# 9V_Power_Supply.net
KiCad netlist of a schematic drawn in EAGLE
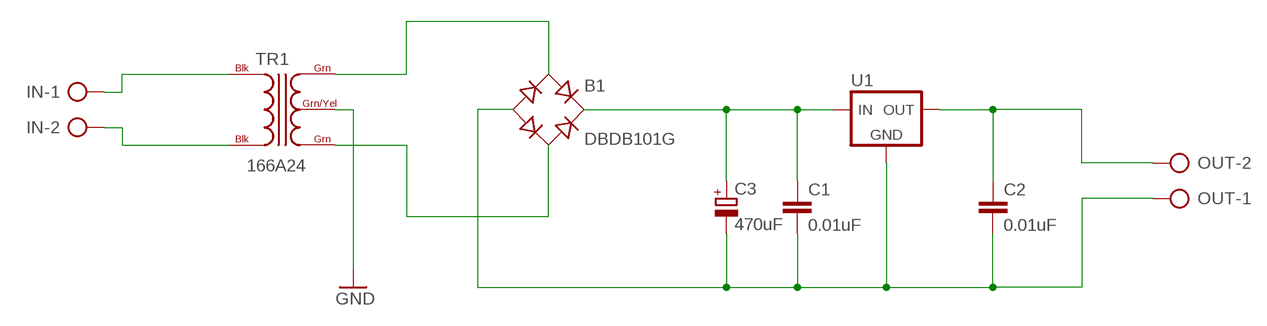
[diagram p0: schematic, sheet 1]

(export (version "E")
  (design (tool "Eeschema 10.0.6"))
  (components
    (comp (ref "B1")
      (value "DBDB101G")
      (footprint "eagle-import:DB")
      (libsource (lib "eagle-import") (part "DB?GDB101"))
    )
    (comp (ref "C1")
      (value "0.01uF")
      (footprint "eagle-import:C025-030X050")
      (libsource (lib "eagle-import") (part "C-EU025-030X050"))
    )
    (comp (ref "C2")
      (value "0.01uF")
      (footprint "eagle-import:C025-030X050")
      (libsource (lib "eagle-import") (part "C-EU025-030X050"))
    )
    (comp (ref "C3")
      (value "470uF")
      (footprint "eagle-import:E2,5-7")
      (libsource (lib "eagle-import") (part "CPOL-EUE2.5-7"))
    )
    (comp (ref "IN")
      (value "AK300/2")
      (footprint "eagle-import:AK300_2")
      (libsource (lib "eagle-import") (part "AK300/2"))
    )
    (comp (ref "OUT")
      (value "AK300/2")
      (footprint "eagle-import:AK300_2")
      (libsource (lib "eagle-import") (part "AK300/2"))
    )
    (comp (ref "TR1")
      (value "166A24")
      (footprint "eagle-import:C2H")
      (libsource (lib "eagle-import") (part "166A24"))
    )
    (comp (ref "U1")
      (value "78XX-TO220H-NH")
      (footprint "eagle-import:TO220BH-NH")
      (libsource (lib "eagle-import") (part "78XX-TO220H-NH"))
    )
  )
  (nets
    (net (code "1") (name "GND") (class "Default")
      (node (ref "B1") (pin "-") (pinfunction "-_-") (pintype "passive"))
      (node (ref "C1") (pin "2") (pinfunction "2_2") (pintype "passive"))
      (node (ref "C2") (pin "2") (pinfunction "2_2") (pintype "passive"))
      (node (ref "C3") (pin "-") (pinfunction "-_-") (pintype "passive"))
      (node (ref "OUT") (pin "1") (pinfunction "KL_1") (pintype "passive"))
      (node (ref "TR1") (pin "GRN/YEL") (pinfunction "GRN/YEL_GRN/YEL") (pintype "passive"))
      (node (ref "U1") (pin "2") (pinfunction "GND_2") (pintype "power_in"))
    )
    (net (code "2") (name "Net-(B1-PadAC1)") (class "Default")
      (node (ref "B1") (pin "AC1") (pinfunction "AC1_AC1") (pintype "passive"))
      (node (ref "TR1") (pin "GRN@1") (pinfunction "GRN_GRN@1") (pintype "passive"))
    )
    (net (code "3") (name "Net-(B1-PadAC2)") (class "Default")
      (node (ref "B1") (pin "AC2") (pinfunction "AC2_AC2") (pintype "passive"))
      (node (ref "TR1") (pin "GRN@2") (pinfunction "GRN_GRN@2") (pintype "passive"))
    )
    (net (code "4") (name "Net-(INA-KL)") (class "Default")
      (node (ref "IN") (pin "1") (pinfunction "KL_1") (pintype "passive"))
      (node (ref "TR1") (pin "BLK@1") (pinfunction "BLK_BLK@1") (pintype "passive"))
    )
    (net (code "5") (name "Net-(INB-KL)") (class "Default")
      (node (ref "IN") (pin "2") (pinfunction "KL_2") (pintype "passive"))
      (node (ref "TR1") (pin "BLK@2") (pinfunction "BLK_BLK@2") (pintype "passive"))
    )
    (net (code "6") (name "Net-(OUTB-KL)") (class "Default")
      (node (ref "C2") (pin "1") (pinfunction "1_1") (pintype "passive"))
      (node (ref "OUT") (pin "2") (pinfunction "KL_2") (pintype "passive"))
      (node (ref "U1") (pin "3") (pinfunction "VOUT_3") (pintype "power_in"))
    )
    (net (code "7") (name "Net-(U1-VIN)") (class "Default")
      (node (ref "B1") (pin "+") (pinfunction "+_+") (pintype "passive"))
      (node (ref "C1") (pin "1") (pinfunction "1_1") (pintype "passive"))
      (node (ref "C3") (pin "+") (pinfunction "+_+") (pintype "passive"))
      (node (ref "U1") (pin "1") (pinfunction "VIN_1") (pintype "power_in"))
    )
  )
)
